# SheetPower.net
KiCad netlist of a schematic drawn in Altium Designer
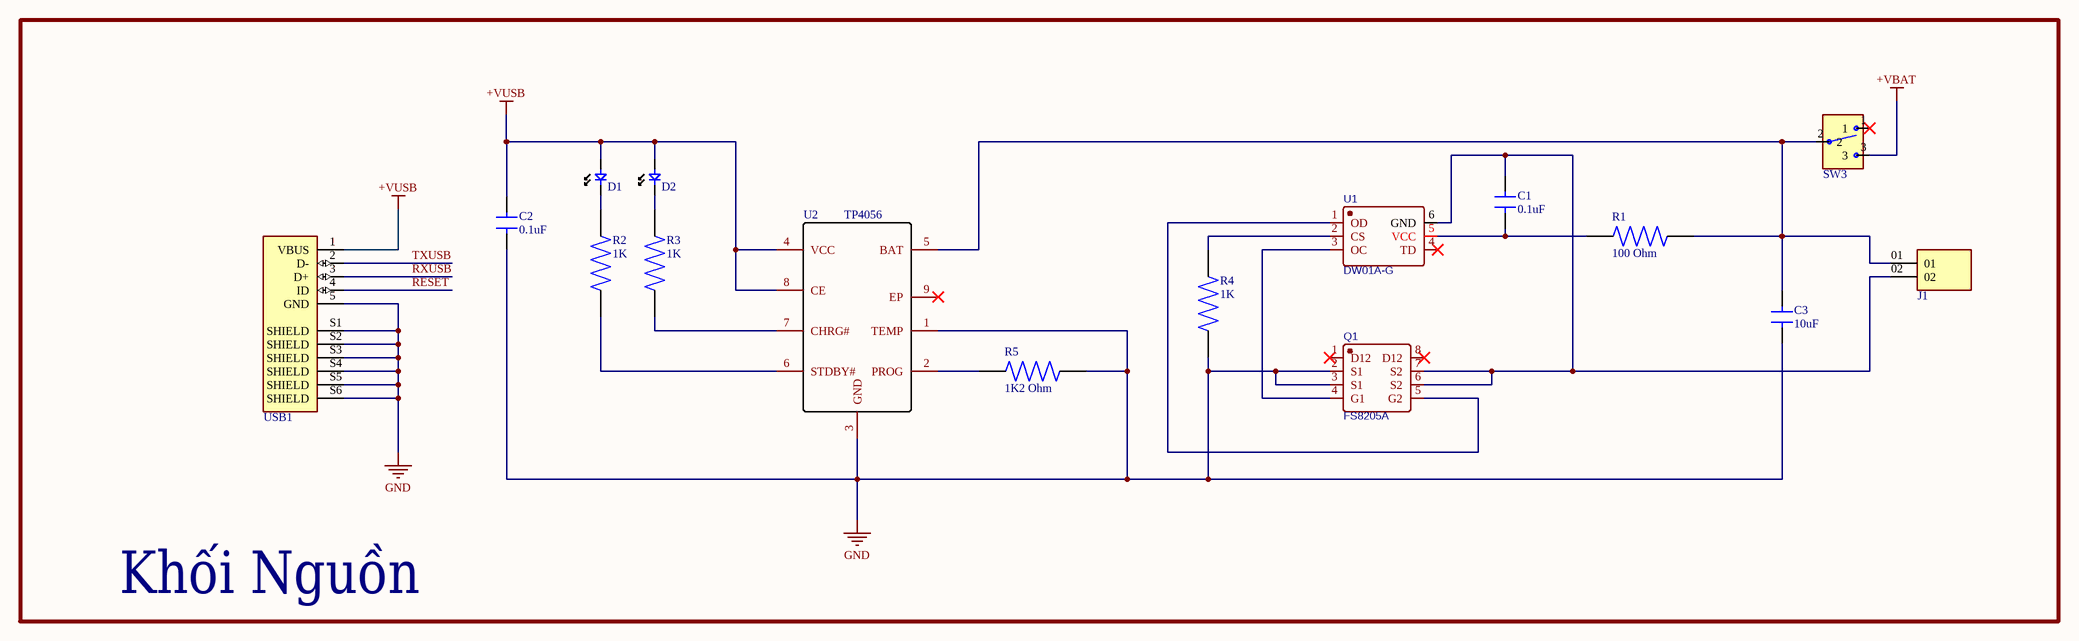
[diagram p0: SheetPower.SchDoc]

(export (version "E")
  (design (tool "Eeschema 10.0.6"))
  (components
    (comp (ref "C1")
      (value "0.1uF")
      (footprint "CAP104 0.1UF 50V")
      (description "Cap Ceramic 0.1uF 50V X7R 10% SMD 2.0 x 1.2 mm 125 C Paper T/R")
      (fields
        (field (name "MANUFACTURER") "KEMET")
        (field (name "MANUFACTURER PART NUMBER") "C0805C104K5RACTU")
      )
      (libsource (lib "SchlibWatch") (part "C0805C104K5RACTU"))
    )
    (comp (ref "C2")
      (value "0.1uF")
      (footprint "CAP104 0.1UF 50V")
      (description "Cap Ceramic 0.1uF 50V X7R 10% SMD 2.0 x 1.2 mm 125 C Paper T/R")
      (fields
        (field (name "MANUFACTURER") "KEMET")
        (field (name "MANUFACTURER PART NUMBER") "C0805C104K5RACTU")
      )
      (libsource (lib "SchlibWatch") (part "C0805C104K5RACTU"))
    )
    (comp (ref "C3")
      (value "10uF")
      (footprint "CAP104 0.1UF 50V")
      (description "CAP CER 10UF 10V Y5V 0805")
      (fields
        (field (name "MANUFACTURER") "Yageo")
        (field (name "MANUFACTURER PART NUMBER") "CC0805ZKY5V6BB106")
      )
      (libsource (lib "SchlibWatch") (part "CC0805ZKY5V6BB106"))
    )
    (comp (ref "D1")
      (value "LED SM 0805 2V 100MCD RED")
      (footprint "LED 0805")
      (description "Red 625nm LED Indication - Discrete 2V 0805 (2012 Metric)")
      (fields
        (field (name "MANUFACTURER") "Visual Communications")
        (field (name "MANUFACTURER PART NUMBER") "LSM0805412V")
      )
      (libsource (lib "SchlibWatch") (part "LSM0805412V"))
    )
    (comp (ref "D2")
      (value "LED SM 0805 2V 100MCD RED")
      (footprint "LED 0805")
      (description "Red 625nm LED Indication - Discrete 2V 0805 (2012 Metric)")
      (fields
        (field (name "MANUFACTURER") "Visual Communications")
        (field (name "MANUFACTURER PART NUMBER") "LSM0805412V")
      )
      (libsource (lib "SchlibWatch") (part "LSM0805412V"))
    )
    (comp (ref "J1")
      (value "HTSW-102-07-H-S")
      (footprint "SAMTEC_HTSW-102-07-H-S")
      (description "Headers & Wire Housings High Temperature PCB Header Strips, 0.100 pitch")
      (fields (field (name "MANUFACTURER") "Samtec"))
      (libsource (lib "SchlibWatch") (part "HTSW-102-07-H-S"))
    )
    (comp (ref "Q1")
      (value "FS8205A")
      (footprint "FS8205A")
      (fields (field (name "BOM_SUPPLIER PART") "C16052"))
      (libsource (lib "SchlibWatch") (part "FS8205A"))
    )
    (comp (ref "R1")
      (value "100 Ohm")
      (footprint "RC0805 1K OHM")
      (description "贴片电阻 100Ω ± 1.00% 0.125W ± 100ppm/℃ 0805")
      (fields
        (field (name "MANUFACTURER") "Yageo")
        (field (name "MANUFACTURER PART NUMBER") "RC0805FR-07100RL")
      )
      (libsource (lib "SchlibWatch") (part "RC0805FR-07100RL"))
    )
    (comp (ref "R2")
      (value "1K")
      (footprint "RC0805 1K OHM")
      (description "贴片电阻 1000Ω ± 1.00% 0.125W ± 100ppm/℃ 0805")
      (fields
        (field (name "MANUFACTURER") "Yageo")
        (field (name "MANUFACTURER PART NUMBER") "RC0805FR-071KL")
      )
      (libsource (lib "SchlibWatch") (part "RC0805FR-071KL"))
    )
    (comp (ref "R3")
      (value "1K")
      (footprint "RC0805 1K OHM")
      (description "贴片电阻 1000Ω ± 1.00% 0.125W ± 100ppm/℃ 0805")
      (fields
        (field (name "MANUFACTURER") "Yageo")
        (field (name "MANUFACTURER PART NUMBER") "RC0805FR-071KL")
      )
      (libsource (lib "SchlibWatch") (part "RC0805FR-071KL"))
    )
    (comp (ref "R4")
      (value "1K")
      (footprint "RC0805 1K OHM")
      (description "贴片电阻 1000Ω ± 1.00% 0.125W ± 100ppm/℃ 0805")
      (fields
        (field (name "MANUFACTURER") "Yageo")
        (field (name "MANUFACTURER PART NUMBER") "RC0805FR-071KL")
      )
      (libsource (lib "SchlibWatch") (part "RC0805FR-071KL"))
    )
    (comp (ref "R5")
      (value "1K2 Ohm")
      (footprint "RC0805 1K OHM")
      (description "Res Thick Film 0805 1.2K Ohm 1% 1/8W ±100ppm/°C Molded SMD SMD Paper T/R")
      (fields
        (field (name "MANUFACTURER") "Vishay Dale")
        (field (name "MANUFACTURER PART NUMBER") "CRCW08051K20FKTA")
      )
      (libsource (lib "SchlibWatch") (part "CRCW08051K20FKTA"))
    )
    (comp (ref "SW3")
      (value "CUS-12TB")
      (footprint "CUS-12B")
      (description "Switch Slide SPDT Side Slide 0.3A 20VDC Gull Wing SMD Embossed T/R")
      (fields (field (name "MANUFACTURER") "Nidec Copal"))
      (libsource (lib "SchlibWatch") (part "CUS-12TB"))
    )
    (comp (ref "U1")
      (value "DW01A-G")
      (footprint "DW01A-G")
      (fields (field (name "BOM_SUPPLIER PART") "C61503") (field (name "CONTRIBUTOR") "LCSC"))
      (libsource (lib "SchlibWatch") (part "DW01A-G"))
    )
    (comp (ref "U2")
      (value "TP4056")
      (footprint "TP4056")
      (description "Vcc=6V Ic=1A")
      (fields (field (name "MANUFACTURER") "TPOWER"))
      (libsource (lib "SchlibWatch") (part "TP4056"))
    )
    (comp (ref "USB1")
      (value "usb micro")
      (footprint "MOLEX_47346-0001")
      (description "Micro-USB B Receptacle with Flange, Bottom Mount, Surface Mount, Lead-Free")
      (fields (field (name "MANUFACTURER") "Molex") (field (name "MANUFACTURER PART NUMBER") "47346-0001"))
      (libsource (lib "SchlibWatch") (part "47346-0001"))
    )
  )
  (nets
    (net (code "1") (name "+VBAT") (class "Default")
      (node (ref "SW3") (pin "3") (pinfunction "3_3") (pintype "passive"))
    )
    (net (code "2") (name "+VUSB") (class "Default")
      (node (ref "C2") (pin "2") (pinfunction "2_2") (pintype "passive"))
      (node (ref "D1") (pin "A") (pinfunction "A_A") (pintype "passive"))
      (node (ref "D2") (pin "A") (pinfunction "A_A") (pintype "passive"))
      (node (ref "U2") (pin "4") (pinfunction "VCC_4") (pintype "passive"))
      (node (ref "U2") (pin "8") (pinfunction "CE_8") (pintype "passive"))
      (node (ref "USB1") (pin "1") (pinfunction "VBUS_1") (pintype "power_in"))
    )
    (net (code "3") (name "/RESET") (class "Default")
      (node (ref "USB1") (pin "4") (pinfunction "ID_4") (pintype "bidirectional"))
    )
    (net (code "4") (name "/RXUSB") (class "Default")
      (node (ref "USB1") (pin "3") (pinfunction "D+_3") (pintype "bidirectional"))
    )
    (net (code "5") (name "/TXUSB") (class "Default")
      (node (ref "USB1") (pin "2") (pinfunction "D-_2") (pintype "bidirectional"))
    )
    (net (code "6") (name "GND") (class "Default")
      (node (ref "C2") (pin "1") (pinfunction "1_1") (pintype "passive"))
      (node (ref "C3") (pin "1") (pinfunction "1_1") (pintype "passive"))
      (node (ref "Q1") (pin "2") (pinfunction "S1_2") (pintype "passive"))
      (node (ref "Q1") (pin "3") (pinfunction "S1_3") (pintype "passive"))
      (node (ref "R4") (pin "1") (pinfunction "1_1") (pintype "passive"))
      (node (ref "R5") (pin "2") (pinfunction "2_2") (pintype "passive"))
      (node (ref "U2") (pin "1") (pinfunction "TEMP_1") (pintype "passive"))
      (node (ref "U2") (pin "3") (pinfunction "GND_3") (pintype "passive"))
      (node (ref "USB1") (pin "5") (pinfunction "GND_5") (pintype "power_in"))
      (node (ref "USB1") (pin "S1") (pinfunction "SHIELD_S1") (pintype "passive"))
      (node (ref "USB1") (pin "S2") (pinfunction "SHIELD_S2") (pintype "passive"))
      (node (ref "USB1") (pin "S3") (pinfunction "SHIELD_S3") (pintype "passive"))
      (node (ref "USB1") (pin "S4") (pinfunction "SHIELD_S4") (pintype "passive"))
      (node (ref "USB1") (pin "S5") (pinfunction "SHIELD_S5") (pintype "passive"))
      (node (ref "USB1") (pin "S6") (pinfunction "SHIELD_S6") (pintype "passive"))
    )
    (net (code "7") (name "Net-(D1-PadK)") (class "Default")
      (node (ref "D1") (pin "K") (pinfunction "K_K") (pintype "passive"))
      (node (ref "R2") (pin "2") (pinfunction "2_2") (pintype "passive"))
    )
    (net (code "8") (name "Net-(D2-PadK)") (class "Default")
      (node (ref "D2") (pin "K") (pinfunction "K_K") (pintype "passive"))
      (node (ref "R3") (pin "2") (pinfunction "2_2") (pintype "passive"))
    )
    (net (code "9") (name "Net-(Q1-G1)") (class "Default")
      (node (ref "Q1") (pin "4") (pinfunction "G1_4") (pintype "passive"))
      (node (ref "U1") (pin "3") (pinfunction "OC_3") (pintype "passive"))
    )
    (net (code "10") (name "Net-(Q1-G2)") (class "Default")
      (node (ref "Q1") (pin "5") (pinfunction "G2_5") (pintype "passive"))
      (node (ref "U1") (pin "1") (pinfunction "OD_1") (pintype "passive"))
    )
    (net (code "11") (name "Net-(U1-CS)") (class "Default")
      (node (ref "R4") (pin "2") (pinfunction "2_2") (pintype "passive"))
      (node (ref "U1") (pin "2") (pinfunction "CS_2") (pintype "passive"))
    )
    (net (code "12") (name "Net-(U1-GND)") (class "Default")
      (node (ref "C1") (pin "2") (pinfunction "2_2") (pintype "passive"))
      (node (ref "J1") (pin "02") (pinfunction "02_02") (pintype "passive"))
      (node (ref "Q1") (pin "6") (pinfunction "S2_6") (pintype "passive"))
      (node (ref "Q1") (pin "7") (pinfunction "S2_7") (pintype "passive"))
      (node (ref "U1") (pin "6") (pinfunction "GND_6") (pintype "passive"))
    )
    (net (code "13") (name "Net-(U1-VCC)") (class "Default")
      (node (ref "C1") (pin "1") (pinfunction "1_1") (pintype "passive"))
      (node (ref "R1") (pin "1") (pinfunction "1_1") (pintype "passive"))
      (node (ref "U1") (pin "5") (pinfunction "VCC_5") (pintype "passive"))
    )
    (net (code "14") (name "Net-(U2-BAT)") (class "Default")
      (node (ref "C3") (pin "2") (pinfunction "2_2") (pintype "passive"))
      (node (ref "J1") (pin "01") (pinfunction "01_01") (pintype "passive"))
      (node (ref "R1") (pin "2") (pinfunction "2_2") (pintype "passive"))
      (node (ref "SW3") (pin "2") (pinfunction "2_2") (pintype "passive"))
      (node (ref "U2") (pin "5") (pinfunction "BAT_5") (pintype "passive"))
    )
    (net (code "15") (name "Net-(U2-CHRG#)") (class "Default")
      (node (ref "R3") (pin "1") (pinfunction "1_1") (pintype "passive"))
      (node (ref "U2") (pin "7") (pinfunction "CHRG#_7") (pintype "passive"))
    )
    (net (code "16") (name "Net-(U2-PROG)") (class "Default")
      (node (ref "R5") (pin "1") (pinfunction "1_1") (pintype "passive"))
      (node (ref "U2") (pin "2") (pinfunction "PROG_2") (pintype "passive"))
    )
    (net (code "17") (name "Net-(U2-STDBY#)") (class "Default")
      (node (ref "R2") (pin "1") (pinfunction "1_1") (pintype "passive"))
      (node (ref "U2") (pin "6") (pinfunction "STDBY#_6") (pintype "passive"))
    )
    (net (code "18") (name "unconnected-(Q1-D12-Pad1)") (class "Default")
      (node (ref "Q1") (pin "1") (pinfunction "D12_1") (pintype "passive+no_connect"))
    )
    (net (code "19") (name "unconnected-(Q1-D12-Pad8)") (class "Default")
      (node (ref "Q1") (pin "8") (pinfunction "D12_8") (pintype "passive+no_connect"))
    )
    (net (code "20") (name "unconnected-(SW3-Pad1)") (class "Default")
      (node (ref "SW3") (pin "1") (pinfunction "1_1") (pintype "passive+no_connect"))
    )
    (net (code "21") (name "unconnected-(U1-TD-Pad4)") (class "Default")
      (node (ref "U1") (pin "4") (pinfunction "TD_4") (pintype "passive+no_connect"))
    )
    (net (code "22") (name "unconnected-(U2-EP-Pad9)") (class "Default")
      (node (ref "U2") (pin "9") (pinfunction "EP_9") (pintype "passive+no_connect"))
    )
  )
)
